# tw_project_starter_template.net
KiCad netlist of a schematic drawn in EAGLE
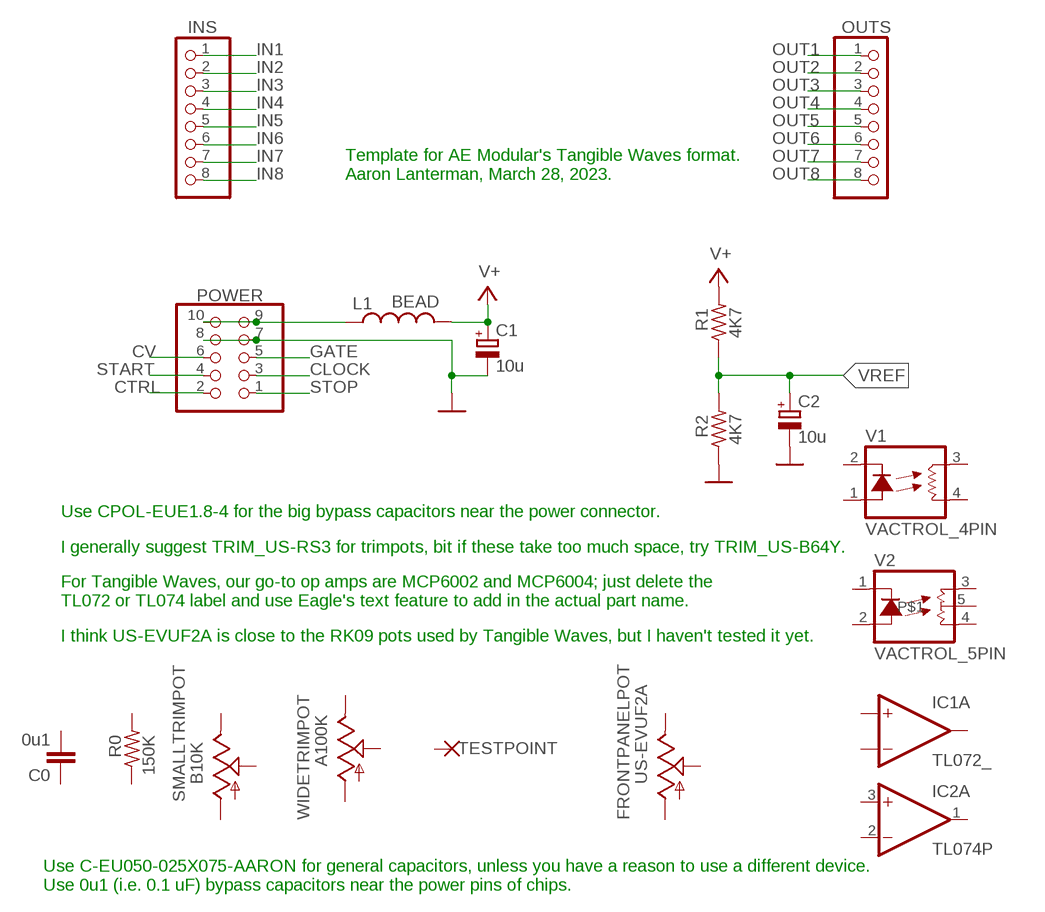
[diagram p0: schematic, sheet 1]

(export (version "E")
  (design (tool "Eeschema 10.0.6"))
  (components
    (comp (ref "C0")
      (value "0u1")
      (footprint "eagle-import:C050-025X075-AARON")
      (libsource (lib "eagle-import") (part "C-EU050-025X075-AARON"))
    )
    (comp (ref "C1")
      (value "10u")
      (footprint "eagle-import:E1,8-4")
      (libsource (lib "eagle-import") (part "CPOL-EUE1.8-4"))
    )
    (comp (ref "C2")
      (value "10u")
      (footprint "eagle-import:E1,8-4")
      (libsource (lib "eagle-import") (part "CPOL-EUE1.8-4"))
    )
    (comp (ref "FRONTPANELPOT")
      (value "US-EVUF2A")
      (footprint "eagle-import:EVUF")
      (libsource (lib "eagle-import") (part "US-EVUAF2"))
    )
    (comp (ref "IC1")
      (value "TL072_")
      (footprint "eagle-import:DIL08")
      (libsource (lib "eagle-import") (part "TL072_"))
    )
    (comp (ref "IC2")
      (value "TL074P")
      (footprint "eagle-import:DIL14")
      (libsource (lib "eagle-import") (part "TL074P"))
    )
    (comp (ref "INS")
      (value "PINHD-1X8")
      (footprint "eagle-import:1X08")
      (libsource (lib "eagle-import") (part "PINHD-1X8"))
    )
    (comp (ref "L1")
      (value "BEAD")
      (footprint "eagle-import:0207_10")
      (libsource (lib "eagle-import") (part "L-US0207/10"))
    )
    (comp (ref "OUTS")
      (value "PINHD-1X8")
      (footprint "eagle-import:1X08")
      (libsource (lib "eagle-import") (part "PINHD-1X8"))
    )
    (comp (ref "POWER")
      (value "PINHD-2X5")
      (footprint "eagle-import:2X05")
      (libsource (lib "eagle-import") (part "PINHD-2X5"))
    )
    (comp (ref "R0")
      (value "150K")
      (footprint "eagle-import:0207_10")
      (libsource (lib "eagle-import") (part "R-US_0207/10"))
    )
    (comp (ref "R1")
      (value "4K7")
      (footprint "eagle-import:0207_10")
      (libsource (lib "eagle-import") (part "R-US_0207/10"))
    )
    (comp (ref "R2")
      (value "4K7")
      (footprint "eagle-import:0207_10")
      (libsource (lib "eagle-import") (part "R-US_0207/10"))
    )
    (comp (ref "SMALLTRIMPOT")
      (value "B10K")
      (footprint "eagle-import:B64Y")
      (libsource (lib "eagle-import") (part "TRIM_US-B64Y"))
    )
    (comp (ref "TESTPOINT")
      (value "IOPAD_AARON")
      (footprint "eagle-import:ELLIPTICALPADSINGLE")
      (libsource (lib "eagle-import") (part "IOPAD_AARON"))
    )
    (comp (ref "V1")
      (value "VACTROL_4PIN")
      (footprint "eagle-import:VACTROL_4PIN_VTL5C")
      (libsource (lib "eagle-import") (part "VACTROL_4PIN"))
    )
    (comp (ref "V2")
      (value "VACTROL_5PIN")
      (footprint "eagle-import:VACTROL_5PIN_VTL5C-2")
      (libsource (lib "eagle-import") (part "VACTROL_5PIN"))
    )
    (comp (ref "WIDETRIMPOT")
      (value "A100K")
      (footprint "eagle-import:S63P")
      (libsource (lib "eagle-import") (part "pot_331_TRIM_US-S63P"))
    )
  )
  (nets
    (net (code "1") (name "/CLOCK") (class "Default")
      (node (ref "POWER") (pin "3") (pinfunction "3_3") (pintype "passive"))
    )
    (net (code "2") (name "/CTRL") (class "Default")
      (node (ref "POWER") (pin "2") (pinfunction "2_2") (pintype "passive"))
    )
    (net (code "3") (name "/CV") (class "Default")
      (node (ref "POWER") (pin "6") (pinfunction "6_6") (pintype "passive"))
    )
    (net (code "4") (name "/GATE") (class "Default")
      (node (ref "POWER") (pin "5") (pinfunction "5_5") (pintype "passive"))
    )
    (net (code "5") (name "/IN1") (class "Default")
      (node (ref "INS") (pin "1") (pinfunction "1_1") (pintype "passive"))
    )
    (net (code "6") (name "/IN2") (class "Default")
      (node (ref "INS") (pin "2") (pinfunction "2_2") (pintype "passive"))
    )
    (net (code "7") (name "/IN3") (class "Default")
      (node (ref "INS") (pin "3") (pinfunction "3_3") (pintype "passive"))
    )
    (net (code "8") (name "/IN4") (class "Default")
      (node (ref "INS") (pin "4") (pinfunction "4_4") (pintype "passive"))
    )
    (net (code "9") (name "/IN5") (class "Default")
      (node (ref "INS") (pin "5") (pinfunction "5_5") (pintype "passive"))
    )
    (net (code "10") (name "/IN6") (class "Default")
      (node (ref "INS") (pin "6") (pinfunction "6_6") (pintype "passive"))
    )
    (net (code "11") (name "/IN7") (class "Default")
      (node (ref "INS") (pin "7") (pinfunction "7_7") (pintype "passive"))
    )
    (net (code "12") (name "/IN8") (class "Default")
      (node (ref "INS") (pin "8") (pinfunction "8_8") (pintype "passive"))
    )
    (net (code "13") (name "/OUT1") (class "Default")
      (node (ref "OUTS") (pin "1") (pinfunction "1_1") (pintype "passive"))
    )
    (net (code "14") (name "/OUT2") (class "Default")
      (node (ref "OUTS") (pin "2") (pinfunction "2_2") (pintype "passive"))
    )
    (net (code "15") (name "/OUT3") (class "Default")
      (node (ref "OUTS") (pin "3") (pinfunction "3_3") (pintype "passive"))
    )
    (net (code "16") (name "/OUT4") (class "Default")
      (node (ref "OUTS") (pin "4") (pinfunction "4_4") (pintype "passive"))
    )
    (net (code "17") (name "/OUT5") (class "Default")
      (node (ref "OUTS") (pin "5") (pinfunction "5_5") (pintype "passive"))
    )
    (net (code "18") (name "/OUT6") (class "Default")
      (node (ref "OUTS") (pin "6") (pinfunction "6_6") (pintype "passive"))
    )
    (net (code "19") (name "/OUT7") (class "Default")
      (node (ref "OUTS") (pin "7") (pinfunction "7_7") (pintype "passive"))
    )
    (net (code "20") (name "/OUT8") (class "Default")
      (node (ref "OUTS") (pin "8") (pinfunction "8_8") (pintype "passive"))
    )
    (net (code "21") (name "/START") (class "Default")
      (node (ref "POWER") (pin "4") (pinfunction "4_4") (pintype "passive"))
    )
    (net (code "22") (name "/STOP") (class "Default")
      (node (ref "POWER") (pin "1") (pinfunction "1_1") (pintype "passive"))
    )
    (net (code "23") (name "GND") (class "Default")
      (node (ref "C1") (pin "-") (pinfunction "-_-") (pintype "passive"))
      (node (ref "C2") (pin "-") (pinfunction "-_-") (pintype "passive"))
      (node (ref "POWER") (pin "7") (pinfunction "7_7") (pintype "passive"))
      (node (ref "POWER") (pin "8") (pinfunction "8_8") (pintype "passive"))
      (node (ref "R2") (pin "1") (pinfunction "1_1") (pintype "passive"))
    )
    (net (code "24") (name "Net-(L1-Pad1)") (class "Default")
      (node (ref "L1") (pin "1") (pinfunction "1_1") (pintype "passive"))
      (node (ref "POWER") (pin "10") (pinfunction "10_10") (pintype "passive"))
      (node (ref "POWER") (pin "9") (pinfunction "9_9") (pintype "passive"))
    )
    (net (code "25") (name "V+") (class "Default")
      (node (ref "C1") (pin "+") (pinfunction "+_+") (pintype "passive"))
      (node (ref "L1") (pin "2") (pinfunction "2_2") (pintype "passive"))
      (node (ref "R1") (pin "2") (pinfunction "2_2") (pintype "passive"))
    )
    (net (code "26") (name "VREF") (class "Default")
      (node (ref "C2") (pin "+") (pinfunction "+_+") (pintype "passive"))
      (node (ref "R1") (pin "1") (pinfunction "1_1") (pintype "passive"))
      (node (ref "R2") (pin "2") (pinfunction "2_2") (pintype "passive"))
    )
    (net (code "27") (name "unconnected-(C0-Pad1)") (class "Default")
      (node (ref "C0") (pin "1") (pinfunction "1_1") (pintype "passive"))
    )
    (net (code "28") (name "unconnected-(C0-Pad2)") (class "Default")
      (node (ref "C0") (pin "2") (pinfunction "2_2") (pintype "passive"))
    )
    (net (code "29") (name "unconnected-(FRONTPANELPOT-A-Pad1)") (class "Default")
      (node (ref "FRONTPANELPOT") (pin "1") (pinfunction "A_1") (pintype "passive"))
    )
    (net (code "30") (name "unconnected-(FRONTPANELPOT-E-Pad3)") (class "Default")
      (node (ref "FRONTPANELPOT") (pin "3") (pinfunction "E_3") (pintype "passive"))
    )
    (net (code "31") (name "unconnected-(FRONTPANELPOT-S-Pad2)") (class "Default")
      (node (ref "FRONTPANELPOT") (pin "2") (pinfunction "S_2") (pintype "passive"))
    )
    (net (code "32") (name "unconnected-(IC1A-+IN-Pad3)") (class "Default")
      (node (ref "IC1") (pin "3") (pinfunction "+IN_3") (pintype "input"))
    )
    (net (code "33") (name "unconnected-(IC1A--IN-Pad2)") (class "Default")
      (node (ref "IC1") (pin "2") (pinfunction "-IN_2") (pintype "input"))
    )
    (net (code "34") (name "unconnected-(IC1A-OUT-Pad1)") (class "Default")
      (node (ref "IC1") (pin "1") (pinfunction "OUT_1") (pintype "output"))
    )
    (net (code "35") (name "unconnected-(IC2A-+IN-Pad3)") (class "Default")
      (node (ref "IC2") (pin "3") (pinfunction "+IN_3") (pintype "input"))
    )
    (net (code "36") (name "unconnected-(IC2A--IN-Pad2)") (class "Default")
      (node (ref "IC2") (pin "2") (pinfunction "-IN_2") (pintype "input"))
    )
    (net (code "37") (name "unconnected-(IC2A-OUT-Pad1)") (class "Default")
      (node (ref "IC2") (pin "1") (pinfunction "OUT_1") (pintype "output"))
    )
    (net (code "38") (name "unconnected-(R0-Pad1)") (class "Default")
      (node (ref "R0") (pin "1") (pinfunction "1_1") (pintype "passive"))
    )
    (net (code "39") (name "unconnected-(R0-Pad2)") (class "Default")
      (node (ref "R0") (pin "2") (pinfunction "2_2") (pintype "passive"))
    )
    (net (code "40") (name "unconnected-(SMALLTRIMPOT-PadA)") (class "Default")
      (node (ref "SMALLTRIMPOT") (pin "A") (pinfunction "A_A") (pintype "passive"))
    )
    (net (code "41") (name "unconnected-(SMALLTRIMPOT-PadE)") (class "Default")
      (node (ref "SMALLTRIMPOT") (pin "E") (pinfunction "E_E") (pintype "passive"))
    )
    (net (code "42") (name "unconnected-(SMALLTRIMPOT-PadS)") (class "Default")
      (node (ref "SMALLTRIMPOT") (pin "S") (pinfunction "S_S") (pintype "passive"))
    )
    (net (code "43") (name "unconnected-(TESTPOINT-P-PadP$1)") (class "Default")
      (node (ref "TESTPOINT") (pin "P$1") (pinfunction "P_P$1") (pintype "passive"))
    )
    (net (code "44") (name "unconnected-(V1-LED+-Pad2)") (class "Default")
      (node (ref "V1") (pin "2") (pinfunction "LED+_2") (pintype "passive"))
    )
    (net (code "45") (name "unconnected-(V1-LED--Pad1)") (class "Default")
      (node (ref "V1") (pin "1") (pinfunction "LED-_1") (pintype "passive"))
    )
    (net (code "46") (name "unconnected-(V1-RES1-Pad3)") (class "Default")
      (node (ref "V1") (pin "3") (pinfunction "RES1_3") (pintype "passive"))
    )
    (net (code "47") (name "unconnected-(V1-RES2-Pad4)") (class "Default")
      (node (ref "V1") (pin "4") (pinfunction "RES2_4") (pintype "passive"))
    )
    (net (code "48") (name "unconnected-(V2-A-Pad1)") (class "Default")
      (node (ref "V2") (pin "1") (pinfunction "A_1") (pintype "passive"))
    )
    (net (code "49") (name "unconnected-(V2-C-Pad2)") (class "Default")
      (node (ref "V2") (pin "2") (pinfunction "C_2") (pintype "passive"))
    )
    (net (code "50") (name "unconnected-(V2-L1-Pad3)") (class "Default")
      (node (ref "V2") (pin "3") (pinfunction "L1_3") (pintype "passive"))
    )
    (net (code "51") (name "unconnected-(V2-L2-Pad4)") (class "Default")
      (node (ref "V2") (pin "4") (pinfunction "L2_4") (pintype "passive"))
    )
    (net (code "52") (name "unconnected-(V2-P$1-Pad5)") (class "Default")
      (node (ref "V2") (pin "5") (pinfunction "P$1_5") (pintype "passive"))
    )
    (net (code "53") (name "unconnected-(WIDETRIMPOT-PadA)") (class "Default")
      (node (ref "WIDETRIMPOT") (pin "A") (pinfunction "A_A") (pintype "passive"))
    )
    (net (code "54") (name "unconnected-(WIDETRIMPOT-PadE)") (class "Default")
      (node (ref "WIDETRIMPOT") (pin "E") (pinfunction "E_E") (pintype "passive"))
    )
    (net (code "55") (name "unconnected-(WIDETRIMPOT-PadS)") (class "Default")
      (node (ref "WIDETRIMPOT") (pin "S") (pinfunction "S_S") (pintype "passive"))
    )
  )
)
